# Soldeertin_dispenser.net
KiCad netlist of a schematic drawn in EAGLE
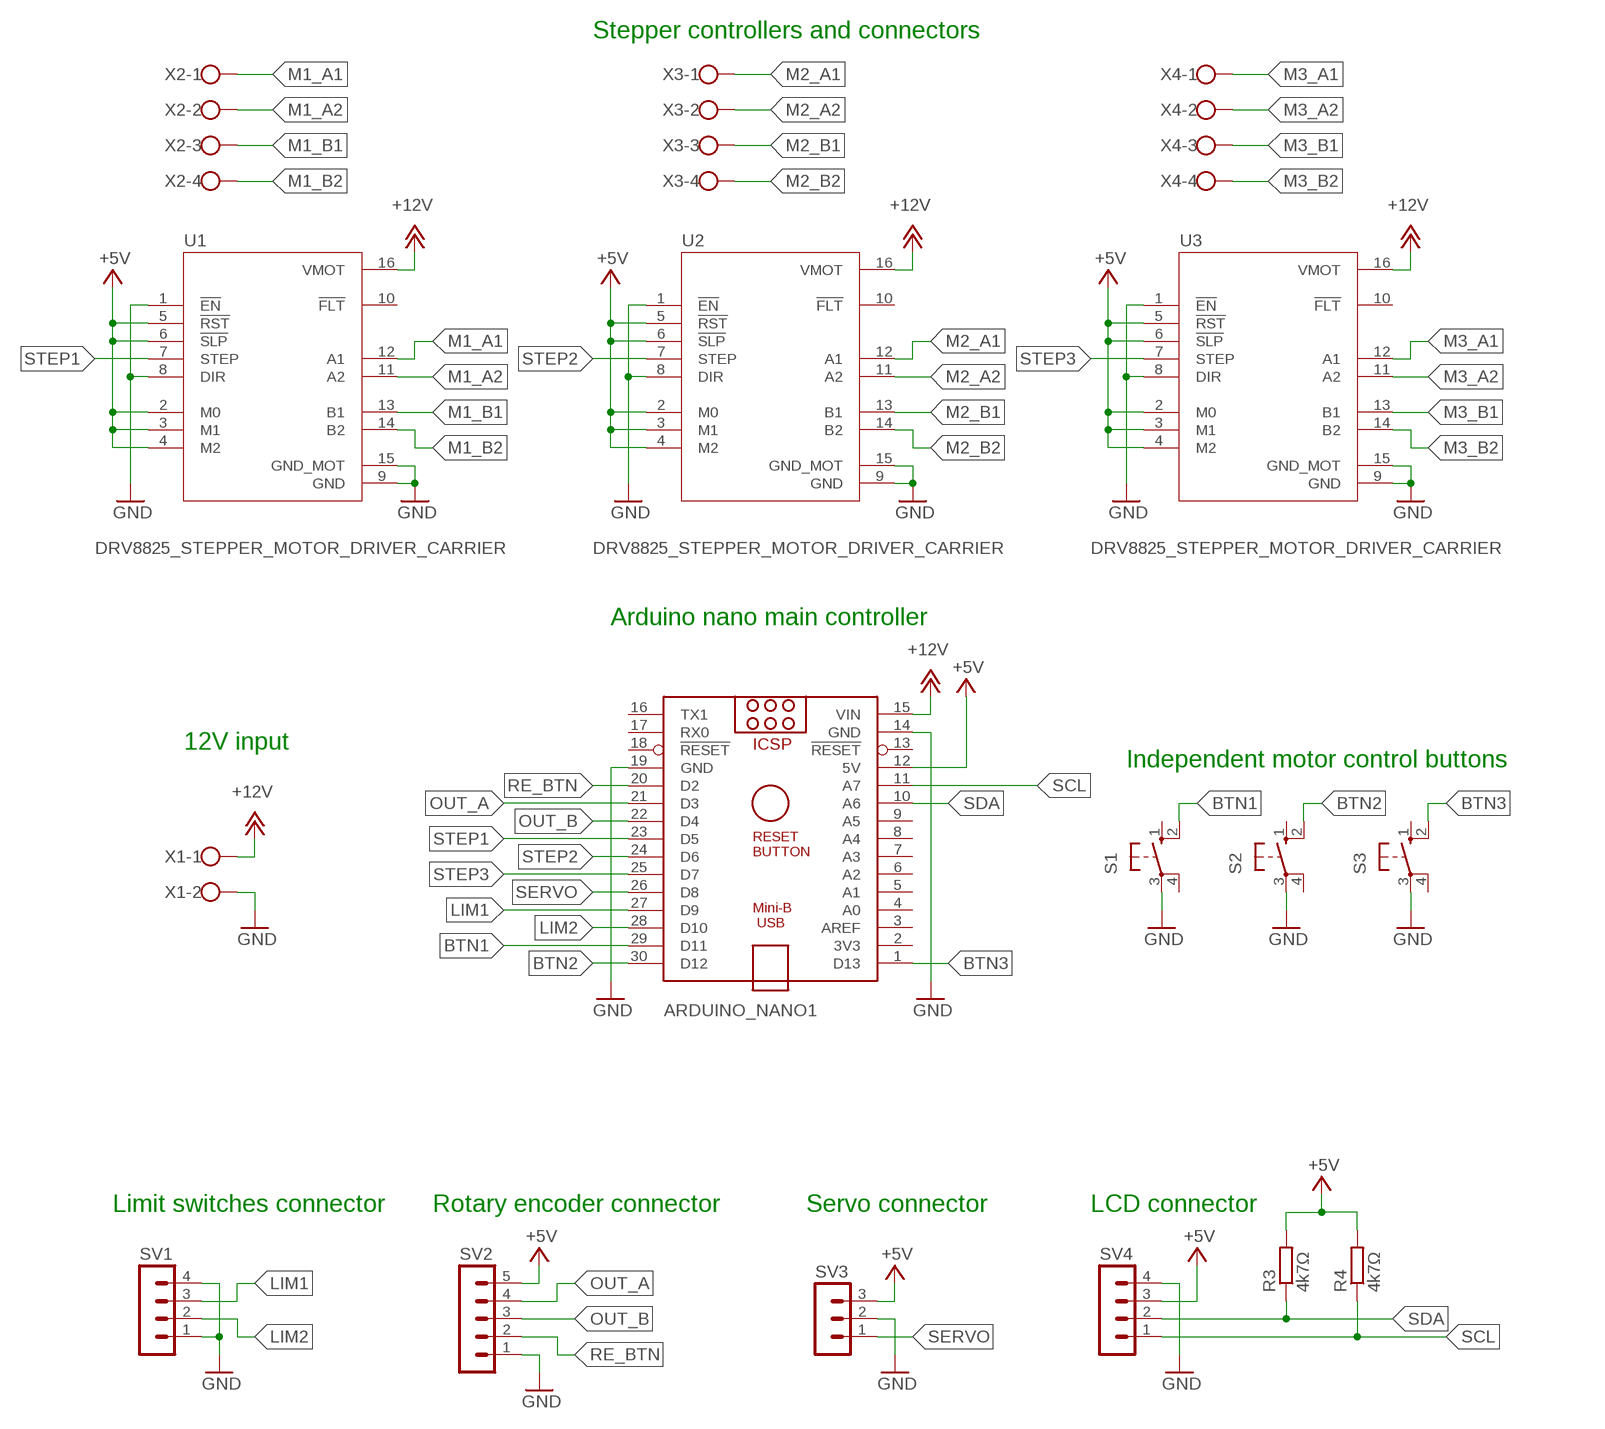
[diagram p0: schematic, sheet 1]

(export (version "E")
  (design (tool "Eeschema 10.0.6"))
  (components
    (comp (ref "ARDUINO_NANO1")
      (value "ARDUINO_NANO")
      (footprint "eagle-import:ARDUINO_NANO")
      (libsource (lib "eagle-import") (part "ARDUINO_NANO"))
    )
    (comp (ref "R3")
      (value "4k7Ω")
      (footprint "eagle-import:0207_10")
      (libsource (lib "eagle-import") (part "R-EU_0207/10"))
    )
    (comp (ref "R4")
      (value "4k7Ω")
      (footprint "eagle-import:0207_10")
      (libsource (lib "eagle-import") (part "R-EU_0207/10"))
    )
    (comp (ref "S1")
      (value "10-XX")
      (footprint "eagle-import:B3F-10XX")
      (fields (field (name "MPN") "B3F-1000"))
      (libsource (lib "eagle-import") (part "10-XX"))
    )
    (comp (ref "S2")
      (value "10-XX")
      (footprint "eagle-import:B3F-10XX")
      (fields (field (name "MPN") "B3F-1000"))
      (libsource (lib "eagle-import") (part "10-XX"))
    )
    (comp (ref "S3")
      (value "10-XX")
      (footprint "eagle-import:B3F-10XX")
      (fields (field (name "MPN") "B3F-1000"))
      (libsource (lib "eagle-import") (part "10-XX"))
    )
    (comp (ref "SV1")
      (value "MA04-1")
      (footprint "eagle-import:MA04-1")
      (libsource (lib "eagle-import") (part "MA04-1"))
    )
    (comp (ref "SV2")
      (value "MA05-1")
      (footprint "eagle-import:MA05-1")
      (libsource (lib "eagle-import") (part "MA05-1"))
    )
    (comp (ref "SV3")
      (value "MA03-1")
      (footprint "eagle-import:MA03-1")
      (libsource (lib "eagle-import") (part "MA03-1"))
    )
    (comp (ref "SV4")
      (value "MA04-1")
      (footprint "eagle-import:MA04-1")
      (libsource (lib "eagle-import") (part "MA04-1"))
    )
    (comp (ref "U1")
      (value "DRV8825_STEPPER_MOTOR_DRIVER_CARRIER")
      (footprint "eagle-import:IC_DRV8825_STEPPER_MOTOR_DRIVER_CARRIER")
      (fields (field (name "MF") "Pololu") (field (name "MP") "DRV8825 STEPPER MOTOR DRIVER CARRIER"))
      (libsource (lib "eagle-import") (part "DRV8825_STEPPER_MOTOR_DRIVER_CARRIER"))
    )
    (comp (ref "U2")
      (value "DRV8825_STEPPER_MOTOR_DRIVER_CARRIER")
      (footprint "eagle-import:IC_DRV8825_STEPPER_MOTOR_DRIVER_CARRIER")
      (fields (field (name "MF") "Pololu") (field (name "MP") "DRV8825 STEPPER MOTOR DRIVER CARRIER"))
      (libsource (lib "eagle-import") (part "DRV8825_STEPPER_MOTOR_DRIVER_CARRIER"))
    )
    (comp (ref "U3")
      (value "DRV8825_STEPPER_MOTOR_DRIVER_CARRIER")
      (footprint "eagle-import:IC_DRV8825_STEPPER_MOTOR_DRIVER_CARRIER")
      (fields (field (name "MF") "Pololu") (field (name "MP") "DRV8825 STEPPER MOTOR DRIVER CARRIER"))
      (libsource (lib "eagle-import") (part "DRV8825_STEPPER_MOTOR_DRIVER_CARRIER"))
    )
    (comp (ref "X1")
      (value "W237-102")
      (footprint "eagle-import:W237-102")
      (fields (field (name "MPN") "237-102"))
      (libsource (lib "eagle-import") (part "W237-102"))
    )
    (comp (ref "X2")
      (value "W237-4")
      (footprint "eagle-import:W237-4")
      (libsource (lib "eagle-import") (part "W237-4"))
    )
    (comp (ref "X3")
      (value "W237-4")
      (footprint "eagle-import:W237-4")
      (libsource (lib "eagle-import") (part "W237-4"))
    )
    (comp (ref "X4")
      (value "W237-4")
      (footprint "eagle-import:W237-4")
      (libsource (lib "eagle-import") (part "W237-4"))
    )
  )
  (nets
    (net (code "1") (name "+5V") (class "Default")
      (node (ref "ARDUINO_NANO1") (pin "12") (pinfunction "5V_12") (pintype "power_in"))
      (node (ref "R3") (pin "2") (pinfunction "2_2") (pintype "passive"))
      (node (ref "R4") (pin "2") (pinfunction "2_2") (pintype "passive"))
      (node (ref "SV2") (pin "5") (pinfunction "5_5") (pintype "passive"))
      (node (ref "SV3") (pin "3") (pinfunction "3_3") (pintype "passive"))
      (node (ref "SV4") (pin "3") (pinfunction "3_3") (pintype "passive"))
      (node (ref "U1") (pin "2") (pinfunction "M0_2") (pintype "input"))
      (node (ref "U1") (pin "3") (pinfunction "M1_3") (pintype "input"))
      (node (ref "U1") (pin "4") (pinfunction "M2_4") (pintype "input"))
      (node (ref "U1") (pin "5") (pinfunction "~{RST}_5") (pintype "input"))
      (node (ref "U1") (pin "6") (pinfunction "~{SLP}_6") (pintype "input"))
      (node (ref "U2") (pin "2") (pinfunction "M0_2") (pintype "input"))
      (node (ref "U2") (pin "3") (pinfunction "M1_3") (pintype "input"))
      (node (ref "U2") (pin "4") (pinfunction "M2_4") (pintype "input"))
      (node (ref "U2") (pin "5") (pinfunction "~{RST}_5") (pintype "input"))
      (node (ref "U2") (pin "6") (pinfunction "~{SLP}_6") (pintype "input"))
      (node (ref "U3") (pin "2") (pinfunction "M0_2") (pintype "input"))
      (node (ref "U3") (pin "3") (pinfunction "M1_3") (pintype "input"))
      (node (ref "U3") (pin "4") (pinfunction "M2_4") (pintype "input"))
      (node (ref "U3") (pin "5") (pinfunction "~{RST}_5") (pintype "input"))
      (node (ref "U3") (pin "6") (pinfunction "~{SLP}_6") (pintype "input"))
    )
    (net (code "2") (name "+12V") (class "Default")
      (node (ref "ARDUINO_NANO1") (pin "15") (pinfunction "VIN_15") (pintype "power_in"))
      (node (ref "U1") (pin "16") (pinfunction "VMOT_16") (pintype "power_in"))
      (node (ref "U2") (pin "16") (pinfunction "VMOT_16") (pintype "power_in"))
      (node (ref "U3") (pin "16") (pinfunction "VMOT_16") (pintype "power_in"))
      (node (ref "X1") (pin "1") (pinfunction "KL_1") (pintype "passive"))
    )
    (net (code "3") (name "BTN1") (class "Default")
      (node (ref "ARDUINO_NANO1") (pin "29") (pinfunction "D11_29") (pintype "bidirectional"))
      (node (ref "S1") (pin "2") (pinfunction "S1_2") (pintype "passive"))
    )
    (net (code "4") (name "BTN2") (class "Default")
      (node (ref "ARDUINO_NANO1") (pin "30") (pinfunction "D12_30") (pintype "bidirectional"))
      (node (ref "S2") (pin "2") (pinfunction "S1_2") (pintype "passive"))
    )
    (net (code "5") (name "BTN3") (class "Default")
      (node (ref "ARDUINO_NANO1") (pin "1") (pinfunction "D13_1") (pintype "bidirectional"))
      (node (ref "S3") (pin "2") (pinfunction "S1_2") (pintype "passive"))
    )
    (net (code "6") (name "GND") (class "Default")
      (node (ref "ARDUINO_NANO1") (pin "14") (pinfunction "GND_14") (pintype "power_in"))
      (node (ref "ARDUINO_NANO1") (pin "19") (pinfunction "GND_19") (pintype "power_in"))
      (node (ref "S1") (pin "3") (pinfunction "P_3") (pintype "passive"))
      (node (ref "S2") (pin "3") (pinfunction "P_3") (pintype "passive"))
      (node (ref "S3") (pin "3") (pinfunction "P_3") (pintype "passive"))
      (node (ref "SV1") (pin "1") (pinfunction "1_1") (pintype "passive"))
      (node (ref "SV1") (pin "4") (pinfunction "4_4") (pintype "passive"))
      (node (ref "SV2") (pin "1") (pinfunction "1_1") (pintype "passive"))
      (node (ref "SV3") (pin "2") (pinfunction "2_2") (pintype "passive"))
      (node (ref "SV4") (pin "4") (pinfunction "4_4") (pintype "passive"))
      (node (ref "U1") (pin "1") (pinfunction "~{EN}_1") (pintype "input"))
      (node (ref "U1") (pin "15") (pinfunction "GND_MOT_15") (pintype "power_in"))
      (node (ref "U1") (pin "8") (pinfunction "DIR_8") (pintype "input"))
      (node (ref "U1") (pin "9") (pinfunction "GND_9") (pintype "power_in"))
      (node (ref "U2") (pin "1") (pinfunction "~{EN}_1") (pintype "input"))
      (node (ref "U2") (pin "15") (pinfunction "GND_MOT_15") (pintype "power_in"))
      (node (ref "U2") (pin "8") (pinfunction "DIR_8") (pintype "input"))
      (node (ref "U2") (pin "9") (pinfunction "GND_9") (pintype "power_in"))
      (node (ref "U3") (pin "1") (pinfunction "~{EN}_1") (pintype "input"))
      (node (ref "U3") (pin "15") (pinfunction "GND_MOT_15") (pintype "power_in"))
      (node (ref "U3") (pin "8") (pinfunction "DIR_8") (pintype "input"))
      (node (ref "U3") (pin "9") (pinfunction "GND_9") (pintype "power_in"))
      (node (ref "X1") (pin "2") (pinfunction "KL_2") (pintype "passive"))
    )
    (net (code "7") (name "LIM1") (class "Default")
      (node (ref "ARDUINO_NANO1") (pin "27") (pinfunction "D9_27") (pintype "bidirectional"))
      (node (ref "SV1") (pin "3") (pinfunction "3_3") (pintype "passive"))
    )
    (net (code "8") (name "LIM2") (class "Default")
      (node (ref "ARDUINO_NANO1") (pin "28") (pinfunction "D10_28") (pintype "bidirectional"))
      (node (ref "SV1") (pin "2") (pinfunction "2_2") (pintype "passive"))
    )
    (net (code "9") (name "M1_A1") (class "Default")
      (node (ref "U1") (pin "12") (pinfunction "A1_12") (pintype "output"))
      (node (ref "X2") (pin "1") (pinfunction "KL_1") (pintype "passive"))
    )
    (net (code "10") (name "M1_A2") (class "Default")
      (node (ref "U1") (pin "11") (pinfunction "A2_11") (pintype "output"))
      (node (ref "X2") (pin "2") (pinfunction "KL_2") (pintype "passive"))
    )
    (net (code "11") (name "M1_B1") (class "Default")
      (node (ref "U1") (pin "13") (pinfunction "B1_13") (pintype "output"))
      (node (ref "X2") (pin "3") (pinfunction "KL_3") (pintype "passive"))
    )
    (net (code "12") (name "M1_B2") (class "Default")
      (node (ref "U1") (pin "14") (pinfunction "B2_14") (pintype "output"))
      (node (ref "X2") (pin "4") (pinfunction "KL_4") (pintype "passive"))
    )
    (net (code "13") (name "M2_A1") (class "Default")
      (node (ref "U2") (pin "12") (pinfunction "A1_12") (pintype "output"))
      (node (ref "X3") (pin "1") (pinfunction "KL_1") (pintype "passive"))
    )
    (net (code "14") (name "M2_A2") (class "Default")
      (node (ref "U2") (pin "11") (pinfunction "A2_11") (pintype "output"))
      (node (ref "X3") (pin "2") (pinfunction "KL_2") (pintype "passive"))
    )
    (net (code "15") (name "M2_B1") (class "Default")
      (node (ref "U2") (pin "13") (pinfunction "B1_13") (pintype "output"))
      (node (ref "X3") (pin "3") (pinfunction "KL_3") (pintype "passive"))
    )
    (net (code "16") (name "M2_B2") (class "Default")
      (node (ref "U2") (pin "14") (pinfunction "B2_14") (pintype "output"))
      (node (ref "X3") (pin "4") (pinfunction "KL_4") (pintype "passive"))
    )
    (net (code "17") (name "M3_A1") (class "Default")
      (node (ref "U3") (pin "12") (pinfunction "A1_12") (pintype "output"))
      (node (ref "X4") (pin "1") (pinfunction "KL_1") (pintype "passive"))
    )
    (net (code "18") (name "M3_A2") (class "Default")
      (node (ref "U3") (pin "11") (pinfunction "A2_11") (pintype "output"))
      (node (ref "X4") (pin "2") (pinfunction "KL_2") (pintype "passive"))
    )
    (net (code "19") (name "M3_B1") (class "Default")
      (node (ref "U3") (pin "13") (pinfunction "B1_13") (pintype "output"))
      (node (ref "X4") (pin "3") (pinfunction "KL_3") (pintype "passive"))
    )
    (net (code "20") (name "M3_B2") (class "Default")
      (node (ref "U3") (pin "14") (pinfunction "B2_14") (pintype "output"))
      (node (ref "X4") (pin "4") (pinfunction "KL_4") (pintype "passive"))
    )
    (net (code "21") (name "OUT_A") (class "Default")
      (node (ref "ARDUINO_NANO1") (pin "21") (pinfunction "D3_21") (pintype "bidirectional"))
      (node (ref "SV2") (pin "4") (pinfunction "4_4") (pintype "passive"))
    )
    (net (code "22") (name "OUT_B") (class "Default")
      (node (ref "ARDUINO_NANO1") (pin "22") (pinfunction "D4_22") (pintype "bidirectional"))
      (node (ref "SV2") (pin "3") (pinfunction "3_3") (pintype "passive"))
    )
    (net (code "23") (name "RE_BTN") (class "Default")
      (node (ref "ARDUINO_NANO1") (pin "20") (pinfunction "D2_20") (pintype "bidirectional"))
      (node (ref "SV2") (pin "2") (pinfunction "2_2") (pintype "passive"))
    )
    (net (code "24") (name "SCL") (class "Default")
      (node (ref "ARDUINO_NANO1") (pin "11") (pinfunction "A7_11") (pintype "bidirectional"))
      (node (ref "R4") (pin "1") (pinfunction "1_1") (pintype "passive"))
      (node (ref "SV4") (pin "1") (pinfunction "1_1") (pintype "passive"))
    )
    (net (code "25") (name "SDA") (class "Default")
      (node (ref "ARDUINO_NANO1") (pin "10") (pinfunction "A6_10") (pintype "bidirectional"))
      (node (ref "R3") (pin "1") (pinfunction "1_1") (pintype "passive"))
      (node (ref "SV4") (pin "2") (pinfunction "2_2") (pintype "passive"))
    )
    (net (code "26") (name "SERVO") (class "Default")
      (node (ref "ARDUINO_NANO1") (pin "26") (pinfunction "D8_26") (pintype "bidirectional"))
      (node (ref "SV3") (pin "1") (pinfunction "1_1") (pintype "passive"))
    )
    (net (code "27") (name "STEP1") (class "Default")
      (node (ref "ARDUINO_NANO1") (pin "23") (pinfunction "D5_23") (pintype "bidirectional"))
      (node (ref "U1") (pin "7") (pinfunction "STEP_7") (pintype "input"))
    )
    (net (code "28") (name "STEP2") (class "Default")
      (node (ref "ARDUINO_NANO1") (pin "24") (pinfunction "D6_24") (pintype "bidirectional"))
      (node (ref "U2") (pin "7") (pinfunction "STEP_7") (pintype "input"))
    )
    (net (code "29") (name "STEP3") (class "Default")
      (node (ref "ARDUINO_NANO1") (pin "25") (pinfunction "D7_25") (pintype "bidirectional"))
      (node (ref "U3") (pin "7") (pinfunction "STEP_7") (pintype "input"))
    )
    (net (code "30") (name "unconnected-(ARDUINO_NANO1-3V3-Pad2)") (class "Default")
      (node (ref "ARDUINO_NANO1") (pin "2") (pinfunction "3V3_2") (pintype "output"))
    )
    (net (code "31") (name "unconnected-(ARDUINO_NANO1-A0-Pad4)") (class "Default")
      (node (ref "ARDUINO_NANO1") (pin "4") (pinfunction "A0_4") (pintype "bidirectional"))
    )
    (net (code "32") (name "unconnected-(ARDUINO_NANO1-A1-Pad5)") (class "Default")
      (node (ref "ARDUINO_NANO1") (pin "5") (pinfunction "A1_5") (pintype "bidirectional"))
    )
    (net (code "33") (name "unconnected-(ARDUINO_NANO1-A2-Pad6)") (class "Default")
      (node (ref "ARDUINO_NANO1") (pin "6") (pinfunction "A2_6") (pintype "bidirectional"))
    )
    (net (code "34") (name "unconnected-(ARDUINO_NANO1-A3-Pad7)") (class "Default")
      (node (ref "ARDUINO_NANO1") (pin "7") (pinfunction "A3_7") (pintype "bidirectional"))
    )
    (net (code "35") (name "unconnected-(ARDUINO_NANO1-A4-Pad8)") (class "Default")
      (node (ref "ARDUINO_NANO1") (pin "8") (pinfunction "A4_8") (pintype "bidirectional"))
    )
    (net (code "36") (name "unconnected-(ARDUINO_NANO1-A5-Pad9)") (class "Default")
      (node (ref "ARDUINO_NANO1") (pin "9") (pinfunction "A5_9") (pintype "bidirectional"))
    )
    (net (code "37") (name "unconnected-(ARDUINO_NANO1-AREF-Pad3)") (class "Default")
      (node (ref "ARDUINO_NANO1") (pin "3") (pinfunction "AREF_3") (pintype "input"))
    )
    (net (code "38") (name "unconnected-(ARDUINO_NANO1-RX0-Pad17)") (class "Default")
      (node (ref "ARDUINO_NANO1") (pin "17") (pinfunction "RX0_17") (pintype "bidirectional"))
    )
    (net (code "39") (name "unconnected-(ARDUINO_NANO1-TX1-Pad16)") (class "Default")
      (node (ref "ARDUINO_NANO1") (pin "16") (pinfunction "TX1_16") (pintype "bidirectional"))
    )
    (net (code "40") (name "unconnected-(ARDUINO_NANO1-~{RESET}-Pad13)") (class "Default")
      (node (ref "ARDUINO_NANO1") (pin "13") (pinfunction "~{RESET}_13") (pintype "input"))
    )
    (net (code "41") (name "unconnected-(ARDUINO_NANO1-~{RESET}-Pad18)") (class "Default")
      (node (ref "ARDUINO_NANO1") (pin "18") (pinfunction "~{RESET}_18") (pintype "input"))
    )
    (net (code "42") (name "unconnected-(S1-P1-Pad4)") (class "Default")
      (node (ref "S1") (pin "4") (pinfunction "P1_4") (pintype "passive"))
    )
    (net (code "43") (name "unconnected-(S1-S-Pad1)") (class "Default")
      (node (ref "S1") (pin "1") (pinfunction "S_1") (pintype "passive"))
    )
    (net (code "44") (name "unconnected-(S2-P1-Pad4)") (class "Default")
      (node (ref "S2") (pin "4") (pinfunction "P1_4") (pintype "passive"))
    )
    (net (code "45") (name "unconnected-(S2-S-Pad1)") (class "Default")
      (node (ref "S2") (pin "1") (pinfunction "S_1") (pintype "passive"))
    )
    (net (code "46") (name "unconnected-(S3-P1-Pad4)") (class "Default")
      (node (ref "S3") (pin "4") (pinfunction "P1_4") (pintype "passive"))
    )
    (net (code "47") (name "unconnected-(S3-S-Pad1)") (class "Default")
      (node (ref "S3") (pin "1") (pinfunction "S_1") (pintype "passive"))
    )
    (net (code "48") (name "unconnected-(U1-~{FLT}-Pad10)") (class "Default")
      (node (ref "U1") (pin "10") (pinfunction "~{FLT}_10") (pintype "output"))
    )
    (net (code "49") (name "unconnected-(U2-~{FLT}-Pad10)") (class "Default")
      (node (ref "U2") (pin "10") (pinfunction "~{FLT}_10") (pintype "output"))
    )
    (net (code "50") (name "unconnected-(U3-~{FLT}-Pad10)") (class "Default")
      (node (ref "U3") (pin "10") (pinfunction "~{FLT}_10") (pintype "output"))
    )
  )
)
